# SCH_DIY_PowerBank_2023-05-28.net
KiCad netlist of a schematic drawn in EasyEDA
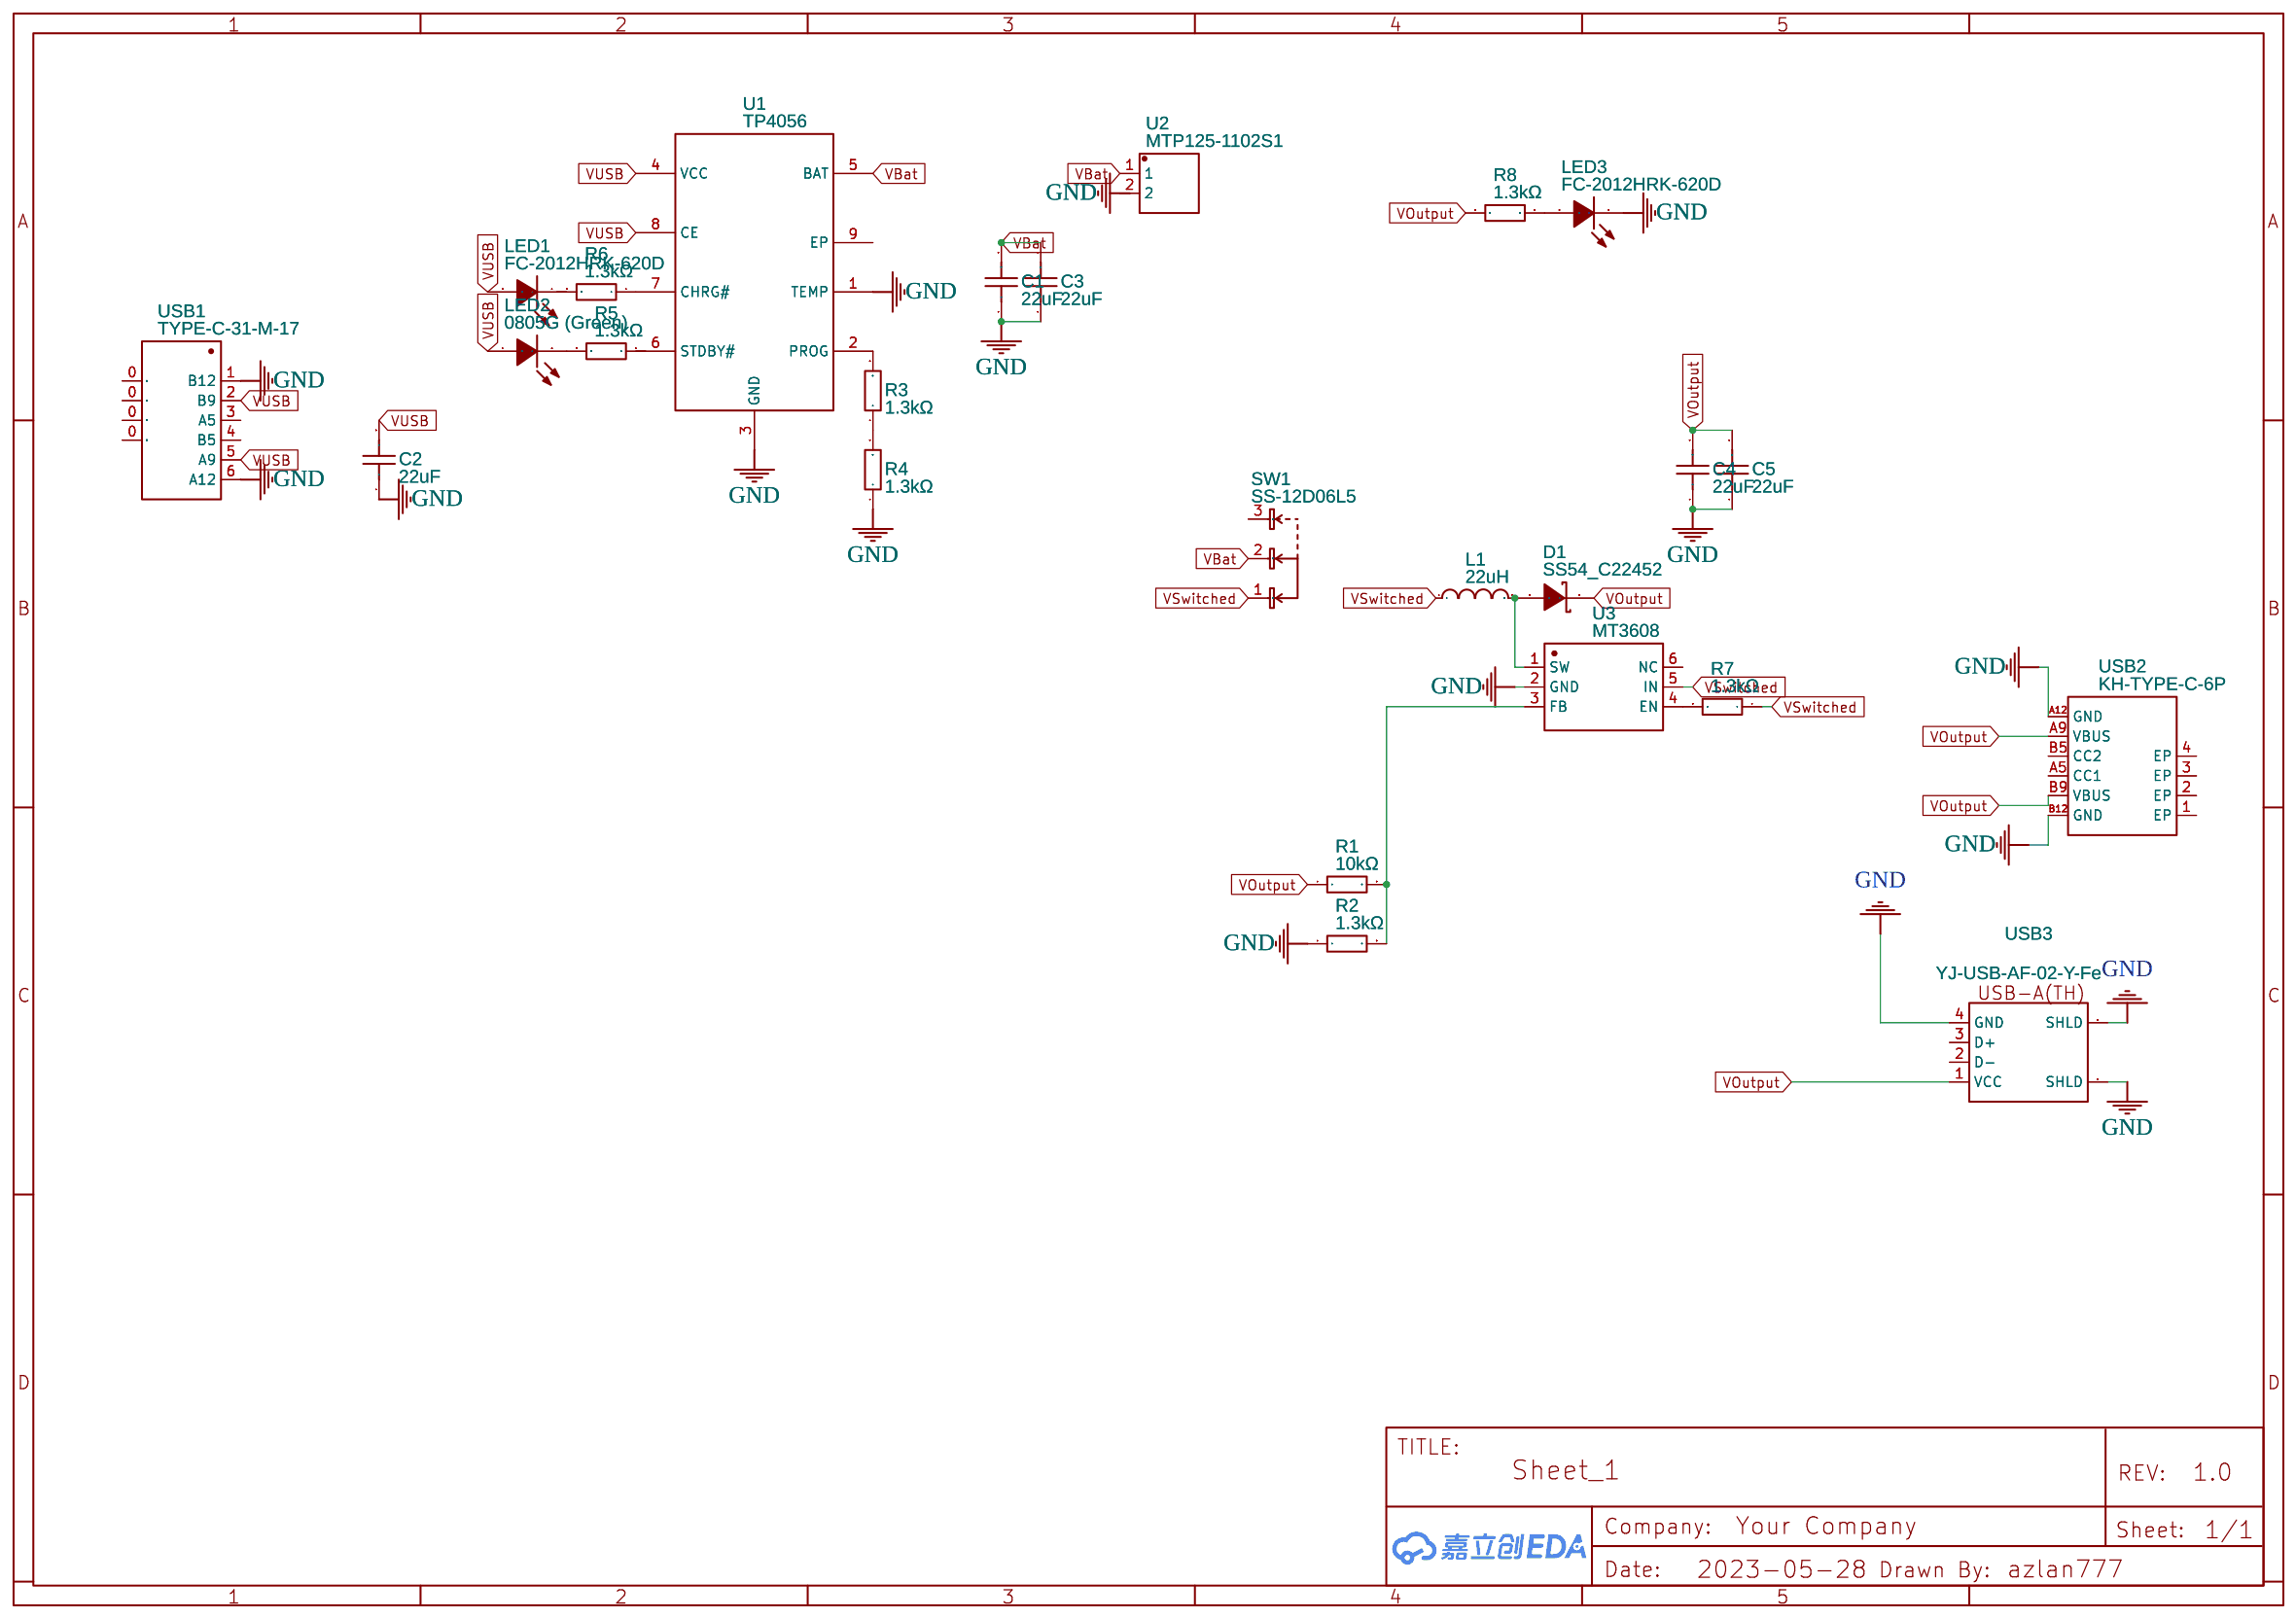
[diagram p0: schematic sheet]

(export (version "E")
  (design (tool "Eeschema 10.0.6"))
  (components
    (comp (ref "C1")
      (value "22uF")
      (fields
        (field (name "BOM_Manufacturer Part") "CL21A226MAQNNNE")
        (field (name "BOM_Supplier Part") "C45783")
      )
      (libsource (lib "") (part "CL21A226MAQNNNE"))
    )
    (comp (ref "C2")
      (value "22uF")
      (fields
        (field (name "BOM_Manufacturer Part") "CL21A226MAQNNNE")
        (field (name "BOM_Supplier Part") "C45783")
      )
      (libsource (lib "") (part "CL21A226MAQNNNE"))
    )
    (comp (ref "C3")
      (value "22uF")
      (fields
        (field (name "BOM_Manufacturer Part") "CL21A226MAQNNNE")
        (field (name "BOM_Supplier Part") "C45783")
      )
      (libsource (lib "") (part "CL21A226MAQNNNE"))
    )
    (comp (ref "C4")
      (value "22uF")
      (fields
        (field (name "BOM_Manufacturer Part") "CL21A226MAQNNNE")
        (field (name "BOM_Supplier Part") "C45783")
      )
      (libsource (lib "") (part "CL21A226MAQNNNE"))
    )
    (comp (ref "C5")
      (value "22uF")
      (fields
        (field (name "BOM_Manufacturer Part") "CL21A226MAQNNNE")
        (field (name "BOM_Supplier Part") "C45783")
      )
      (libsource (lib "") (part "CL21A226MAQNNNE"))
    )
    (comp (ref "D1")
      (value "SS54_C22452")
      (fields (field (name "BOM_Manufacturer Part") "SS54") (field (name "BOM_Supplier Part") "C22452"))
      (libsource (lib "") (part "SS54_C22452"))
    )
    (comp (ref "L1")
      (value "22uH")
      (fields
        (field (name "BOM_Manufacturer Part") "JSHC0650H-220M-G")
        (field (name "BOM_Supplier Part") "C334097")
      )
      (libsource (lib "") (part "JSHC0650H-220M-G"))
    )
    (comp (ref "LED1")
      (value "FC-2012HRK-620D")
      (fields (field (name "BOM_Manufacturer Part") "NCD0805R1") (field (name "BOM_Supplier Part") "C84256"))
      (libsource (lib "") (part "FC-2012HRK-620D"))
    )
    (comp (ref "LED2")
      (value "0805G (Green)")
      (fields (field (name "BOM_Manufacturer Part") "KT-0805翠绿") (field (name "BOM_Supplier Part") "C2297"))
      (libsource (lib "") (part "0805G (Green)"))
    )
    (comp (ref "LED3")
      (value "FC-2012HRK-620D")
      (fields (field (name "BOM_Manufacturer Part") "NCD0805R1") (field (name "BOM_Supplier Part") "C84256"))
      (libsource (lib "") (part "FC-2012HRK-620D"))
    )
    (comp (ref "R1")
      (value "10kΩ")
      (fields
        (field (name "BOM_Manufacturer Part") "0603WAF1002T5E")
        (field (name "BOM_Supplier Part") "C25804")
      )
      (libsource (lib "") (part "0603WAF1002T5E"))
    )
    (comp (ref "R2")
      (value "1.3kΩ")
      (fields
        (field (name "BOM_Manufacturer Part") "CF1/4W-1.3KΩ±5% T")
        (field (name "BOM_Supplier Part") "C120058")
      )
      (libsource (lib "") (part "CF1/4W-1.3KΩ±5% T52"))
    )
    (comp (ref "R3")
      (value "1.3kΩ")
      (fields
        (field (name "BOM_Manufacturer Part") "CF1/4W-1.3KΩ±5% T")
        (field (name "BOM_Supplier Part") "C120058")
      )
      (libsource (lib "") (part "CF1/4W-1.3KΩ±5% T52_2"))
    )
    (comp (ref "R4")
      (value "1.3kΩ")
      (fields
        (field (name "BOM_Manufacturer Part") "CF1/4W-1.3KΩ±5% T")
        (field (name "BOM_Supplier Part") "C120058")
      )
      (libsource (lib "") (part "CF1/4W-1.3KΩ±5% T52_2"))
    )
    (comp (ref "R5")
      (value "1.3kΩ")
      (fields
        (field (name "BOM_Manufacturer Part") "CF1/4W-1.3KΩ±5% T")
        (field (name "BOM_Supplier Part") "C120058")
      )
      (libsource (lib "") (part "CF1/4W-1.3KΩ±5% T52_1"))
    )
    (comp (ref "R6")
      (value "1.3kΩ")
      (fields
        (field (name "BOM_Manufacturer Part") "CF1/4W-1.3KΩ±5% T")
        (field (name "BOM_Supplier Part") "C120058")
      )
      (libsource (lib "") (part "CF1/4W-1.3KΩ±5% T52_1"))
    )
    (comp (ref "R7")
      (value "1.3kΩ")
      (fields
        (field (name "BOM_Manufacturer Part") "CF1/4W-1.3KΩ±5% T")
        (field (name "BOM_Supplier Part") "C120058")
      )
      (libsource (lib "") (part "CF1/4W-1.3KΩ±5% T52_1"))
    )
    (comp (ref "R8")
      (value "1.3kΩ")
      (fields
        (field (name "BOM_Manufacturer Part") "CF1/4W-1.3KΩ±5% T")
        (field (name "BOM_Supplier Part") "C120058")
      )
      (libsource (lib "") (part "CF1/4W-1.3KΩ±5% T52_1"))
    )
    (comp (ref "SW1")
      (value "SS-12D06L5")
      (fields (field (name "BOM_Supplier Part") "C319015"))
      (libsource (lib "") (part "SS-12D06L5"))
    )
    (comp (ref "U1")
      (value "TP4056")
      (fields
        (field (name "BOM_Manufacturer Part") "TP4056-42-ESOP8")
        (field (name "BOM_Supplier Part") "C16581")
      )
      (libsource (lib "") (part "TP4056"))
    )
    (comp (ref "U2")
      (value "MTP125-1102S1")
      (fields (field (name "BOM_Supplier Part") "C358684"))
      (libsource (lib "") (part "MTP125-1102S1"))
    )
    (comp (ref "U3")
      (value "MT3608")
      (fields (field (name "BOM_Supplier Part") "C84817"))
      (libsource (lib "") (part "MT3608"))
    )
    (comp (ref "USB1")
      (value "TYPE-C-31-M-17")
      (fields (field (name "BOM_Supplier Part") "C283540"))
      (libsource (lib "") (part "TYPE-C-31-M-17"))
    )
    (comp (ref "USB2")
      (value "KH-TYPE-C-6P")
      (fields (field (name "BOM_Supplier Part") "C709355"))
      (libsource (lib "") (part "KH-TYPE-C-6P"))
    )
    (comp (ref "USB3")
      (value "YJ-USB-AF-02-Y-Fe")
      (fields (field (name "BOM_Supplier Part") "C2345"))
      (libsource (lib "") (part "YJ-USB-AF-02-Y-Fe"))
    )
  )
  (nets
    (net (code "1") (name "GND") (class "Default")
      (node (ref "C1") (pin "1") (pinfunction "1_1") (pintype "unspecified"))
      (node (ref "C2") (pin "1") (pinfunction "1_1") (pintype "unspecified"))
      (node (ref "C3") (pin "1") (pinfunction "1_1") (pintype "unspecified"))
      (node (ref "C4") (pin "1") (pinfunction "1_1") (pintype "unspecified"))
      (node (ref "C5") (pin "1") (pinfunction "1_1") (pintype "unspecified"))
      (node (ref "LED3") (pin "1") (pinfunction "-_1") (pintype "unspecified"))
      (node (ref "R2") (pin "1") (pinfunction "1_1") (pintype "unspecified"))
      (node (ref "R4") (pin "1") (pinfunction "1_1") (pintype "unspecified"))
      (node (ref "U1") (pin "1") (pinfunction "TEMP_1") (pintype "unspecified"))
      (node (ref "U1") (pin "3") (pinfunction "GND_3") (pintype "unspecified"))
      (node (ref "U2") (pin "2") (pinfunction "2_2") (pintype "unspecified"))
      (node (ref "U3") (pin "2") (pinfunction "GND_2") (pintype "unspecified"))
      (node (ref "USB1") (pin "1") (pinfunction "B12_1") (pintype "unspecified"))
      (node (ref "USB1") (pin "6") (pinfunction "A12_6") (pintype "unspecified"))
      (node (ref "USB2") (pin "A12") (pinfunction "GND_A12") (pintype "unspecified"))
      (node (ref "USB2") (pin "B12") (pinfunction "GND_B12") (pintype "unspecified"))
      (node (ref "USB3") (pin "0") (pinfunction "SHLD_0") (pintype "unspecified"))
      (node (ref "USB3") (pin "4") (pinfunction "GND_4") (pintype "input"))
    )
    (net (code "2") (name "Net-(D1-A)") (class "Default")
      (node (ref "D1") (pin "1") (pinfunction "A_1") (pintype "unspecified"))
      (node (ref "L1") (pin "2") (pinfunction "2_2") (pintype "unspecified"))
      (node (ref "U3") (pin "1") (pinfunction "SW_1") (pintype "unspecified"))
    )
    (net (code "3") (name "Net-(LED1--)") (class "Default")
      (node (ref "LED1") (pin "1") (pinfunction "-_1") (pintype "unspecified"))
      (node (ref "R6") (pin "2") (pinfunction "2_2") (pintype "unspecified"))
    )
    (net (code "4") (name "Net-(LED2-K)") (class "Default")
      (node (ref "LED2") (pin "2") (pinfunction "K_2") (pintype "unspecified"))
      (node (ref "R5") (pin "2") (pinfunction "2_2") (pintype "unspecified"))
    )
    (net (code "5") (name "Net-(LED3-+)") (class "Default")
      (node (ref "LED3") (pin "2") (pinfunction "+_2") (pintype "unspecified"))
      (node (ref "R8") (pin "1") (pinfunction "1_1") (pintype "unspecified"))
    )
    (net (code "6") (name "Net-(R3-Pad1)") (class "Default")
      (node (ref "R3") (pin "1") (pinfunction "1_1") (pintype "unspecified"))
      (node (ref "R4") (pin "2") (pinfunction "2_2") (pintype "unspecified"))
    )
    (net (code "7") (name "Net-(U1-CHRG#)") (class "Default")
      (node (ref "R6") (pin "1") (pinfunction "1_1") (pintype "unspecified"))
      (node (ref "U1") (pin "7") (pinfunction "CHRG#_7") (pintype "unspecified"))
    )
    (net (code "8") (name "Net-(U1-PROG)") (class "Default")
      (node (ref "R3") (pin "2") (pinfunction "2_2") (pintype "unspecified"))
      (node (ref "U1") (pin "2") (pinfunction "PROG_2") (pintype "unspecified"))
    )
    (net (code "9") (name "Net-(U1-STDBY#)") (class "Default")
      (node (ref "R5") (pin "1") (pinfunction "1_1") (pintype "unspecified"))
      (node (ref "U1") (pin "6") (pinfunction "STDBY#_6") (pintype "unspecified"))
    )
    (net (code "10") (name "Net-(U3-EN)") (class "Default")
      (node (ref "R7") (pin "2") (pinfunction "2_2") (pintype "unspecified"))
      (node (ref "U3") (pin "4") (pinfunction "EN_4") (pintype "unspecified"))
    )
    (net (code "11") (name "Net-(U3-FB)") (class "Default")
      (node (ref "R1") (pin "2") (pinfunction "2_2") (pintype "input"))
      (node (ref "R2") (pin "2") (pinfunction "2_2") (pintype "unspecified"))
      (node (ref "U3") (pin "3") (pinfunction "FB_3") (pintype "unspecified"))
    )
    (net (code "12") (name "VBat") (class "Default")
      (node (ref "C1") (pin "2") (pinfunction "2_2") (pintype "unspecified"))
      (node (ref "C3") (pin "2") (pinfunction "2_2") (pintype "unspecified"))
      (node (ref "SW1") (pin "2") (pinfunction "2_2") (pintype "unspecified"))
      (node (ref "U1") (pin "5") (pinfunction "BAT_5") (pintype "unspecified"))
      (node (ref "U2") (pin "1") (pinfunction "1_1") (pintype "unspecified"))
    )
    (net (code "13") (name "VOutput") (class "Default")
      (node (ref "C4") (pin "2") (pinfunction "2_2") (pintype "unspecified"))
      (node (ref "C5") (pin "2") (pinfunction "2_2") (pintype "unspecified"))
      (node (ref "D1") (pin "2") (pinfunction "K_2") (pintype "unspecified"))
      (node (ref "R1") (pin "1") (pinfunction "1_1") (pintype "input"))
      (node (ref "R8") (pin "2") (pinfunction "2_2") (pintype "unspecified"))
      (node (ref "USB2") (pin "A9") (pinfunction "VBUS_A9") (pintype "unspecified"))
      (node (ref "USB2") (pin "B9") (pinfunction "VBUS_B9") (pintype "unspecified"))
      (node (ref "USB3") (pin "1") (pinfunction "VCC_1") (pintype "input"))
    )
    (net (code "14") (name "VSwitched") (class "Default")
      (node (ref "L1") (pin "1") (pinfunction "1_1") (pintype "unspecified"))
      (node (ref "R7") (pin "1") (pinfunction "1_1") (pintype "unspecified"))
      (node (ref "SW1") (pin "1") (pinfunction "1_1") (pintype "unspecified"))
      (node (ref "U3") (pin "5") (pinfunction "IN_5") (pintype "unspecified"))
    )
    (net (code "15") (name "VUSB") (class "Default")
      (node (ref "C2") (pin "2") (pinfunction "2_2") (pintype "unspecified"))
      (node (ref "LED1") (pin "2") (pinfunction "+_2") (pintype "unspecified"))
      (node (ref "LED2") (pin "1") (pinfunction "A_1") (pintype "unspecified"))
      (node (ref "U1") (pin "4") (pinfunction "VCC_4") (pintype "unspecified"))
      (node (ref "U1") (pin "8") (pinfunction "CE_8") (pintype "unspecified"))
      (node (ref "USB1") (pin "2") (pinfunction "B9_2") (pintype "unspecified"))
      (node (ref "USB1") (pin "5") (pinfunction "A9_5") (pintype "unspecified"))
    )
    (net (code "16") (name "unconnected-(SW1-Pad3)") (class "Default")
      (node (ref "SW1") (pin "3") (pinfunction "3_3") (pintype "unspecified"))
    )
    (net (code "17") (name "unconnected-(U1-EP-Pad9)") (class "Default")
      (node (ref "U1") (pin "9") (pinfunction "EP_9") (pintype "unspecified"))
    )
    (net (code "18") (name "unconnected-(U3-NC-Pad6)") (class "Default")
      (node (ref "U3") (pin "6") (pinfunction "NC_6") (pintype "unspecified"))
    )
    (net (code "19") (name "unconnected-(USB1-A5-Pad3)") (class "Default")
      (node (ref "USB1") (pin "3") (pinfunction "A5_3") (pintype "unspecified"))
    )
    (net (code "20") (name "unconnected-(USB1-B5-Pad4)") (class "Default")
      (node (ref "USB1") (pin "4") (pinfunction "B5_4") (pintype "unspecified"))
    )
    (net (code "21") (name "unconnected-(USB1-Pad0)") (class "Default")
      (node (ref "USB1") (pin "0") (pinfunction "0_0") (pintype "unspecified"))
    )
    (net (code "22") (name "unconnected-(USB1-Pad0)_1") (class "Default")
      (node (ref "USB1") (pin "0") (pinfunction "0_0") (pintype "unspecified"))
    )
    (net (code "23") (name "unconnected-(USB1-Pad0)_2") (class "Default")
      (node (ref "USB1") (pin "0") (pinfunction "0_0") (pintype "unspecified"))
    )
    (net (code "24") (name "unconnected-(USB1-Pad0)_3") (class "Default")
      (node (ref "USB1") (pin "0") (pinfunction "0_0") (pintype "unspecified"))
    )
    (net (code "25") (name "unconnected-(USB2-CC1-PadA5)") (class "Default")
      (node (ref "USB2") (pin "A5") (pinfunction "CC1_A5") (pintype "unspecified"))
    )
    (net (code "26") (name "unconnected-(USB2-CC2-PadB5)") (class "Default")
      (node (ref "USB2") (pin "B5") (pinfunction "CC2_B5") (pintype "unspecified"))
    )
    (net (code "27") (name "unconnected-(USB2-EP-Pad1)") (class "Default")
      (node (ref "USB2") (pin "1") (pinfunction "EP_1") (pintype "unspecified"))
    )
    (net (code "28") (name "unconnected-(USB2-EP-Pad2)") (class "Default")
      (node (ref "USB2") (pin "2") (pinfunction "EP_2") (pintype "unspecified"))
    )
    (net (code "29") (name "unconnected-(USB2-EP-Pad3)") (class "Default")
      (node (ref "USB2") (pin "3") (pinfunction "EP_3") (pintype "unspecified"))
    )
    (net (code "30") (name "unconnected-(USB2-EP-Pad4)") (class "Default")
      (node (ref "USB2") (pin "4") (pinfunction "EP_4") (pintype "unspecified"))
    )
    (net (code "31") (name "unconnected-(USB3-D+-Pad3)") (class "Default")
      (node (ref "USB3") (pin "3") (pinfunction "D+_3") (pintype "input"))
    )
    (net (code "32") (name "unconnected-(USB3-D--Pad2)") (class "Default")
      (node (ref "USB3") (pin "2") (pinfunction "D-_2") (pintype "input"))
    )
  )
)
